# lazer.net
KiCad netlist of a schematic drawn in EAGLE
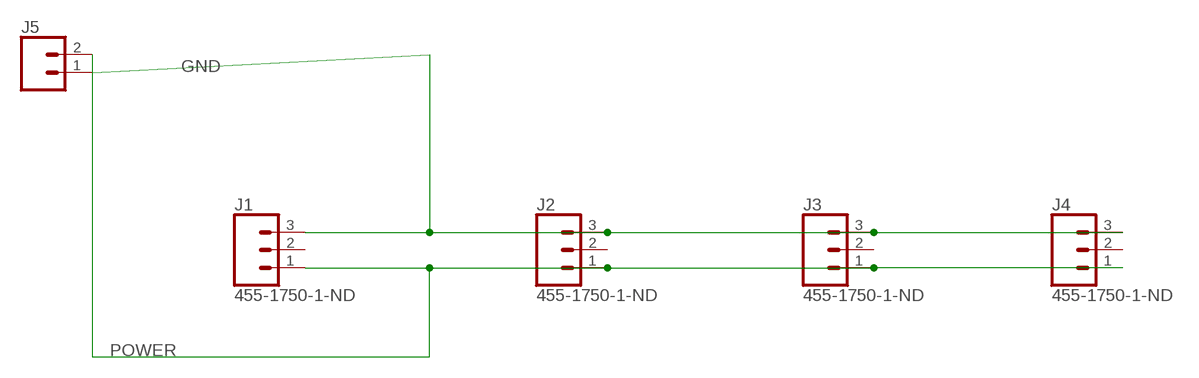
[diagram p0: schematic, sheet 1]

(export (version "E")
  (design (tool "Eeschema 10.0.6"))
  (components
    (comp (ref "J1")
      (value "455-1750-1-ND")
      (footprint "eagle-import:1X03")
      (libsource (lib "eagle-import") (part "CONN_03"))
    )
    (comp (ref "J2")
      (value "455-1750-1-ND")
      (footprint "eagle-import:1X03")
      (libsource (lib "eagle-import") (part "CONN_03"))
    )
    (comp (ref "J3")
      (value "455-1750-1-ND")
      (footprint "eagle-import:1X03")
      (libsource (lib "eagle-import") (part "CONN_03"))
    )
    (comp (ref "J4")
      (value "455-1750-1-ND")
      (footprint "eagle-import:1X03")
      (libsource (lib "eagle-import") (part "CONN_03"))
    )
    (comp (ref "J5")
      (value "CONN_02")
      (footprint "eagle-import:1X02")
      (libsource (lib "eagle-import") (part "CONN_02"))
    )
  )
  (nets
    (net (code "1") (name "/GND") (class "Default")
      (node (ref "J1") (pin "3") (pinfunction "3_3") (pintype "passive"))
      (node (ref "J2") (pin "3") (pinfunction "3_3") (pintype "passive"))
      (node (ref "J3") (pin "3") (pinfunction "3_3") (pintype "passive"))
      (node (ref "J4") (pin "3") (pinfunction "3_3") (pintype "passive"))
      (node (ref "J5") (pin "1") (pinfunction "1_1") (pintype "passive"))
    )
    (net (code "2") (name "/POWER") (class "Default")
      (node (ref "J1") (pin "1") (pinfunction "1_1") (pintype "passive"))
      (node (ref "J2") (pin "1") (pinfunction "1_1") (pintype "passive"))
      (node (ref "J3") (pin "1") (pinfunction "1_1") (pintype "passive"))
      (node (ref "J4") (pin "1") (pinfunction "1_1") (pintype "passive"))
      (node (ref "J5") (pin "2") (pinfunction "2_2") (pintype "passive"))
    )
    (net (code "3") (name "unconnected-(J1-Pad2)") (class "Default")
      (node (ref "J1") (pin "2") (pinfunction "2_2") (pintype "passive"))
    )
    (net (code "4") (name "unconnected-(J2-Pad2)") (class "Default")
      (node (ref "J2") (pin "2") (pinfunction "2_2") (pintype "passive"))
    )
    (net (code "5") (name "unconnected-(J3-Pad2)") (class "Default")
      (node (ref "J3") (pin "2") (pinfunction "2_2") (pintype "passive"))
    )
    (net (code "6") (name "unconnected-(J4-Pad2)") (class "Default")
      (node (ref "J4") (pin "2") (pinfunction "2_2") (pintype "passive"))
    )
  )
)
